# Expanders.net
KiCad netlist of a schematic drawn in Altium Designer
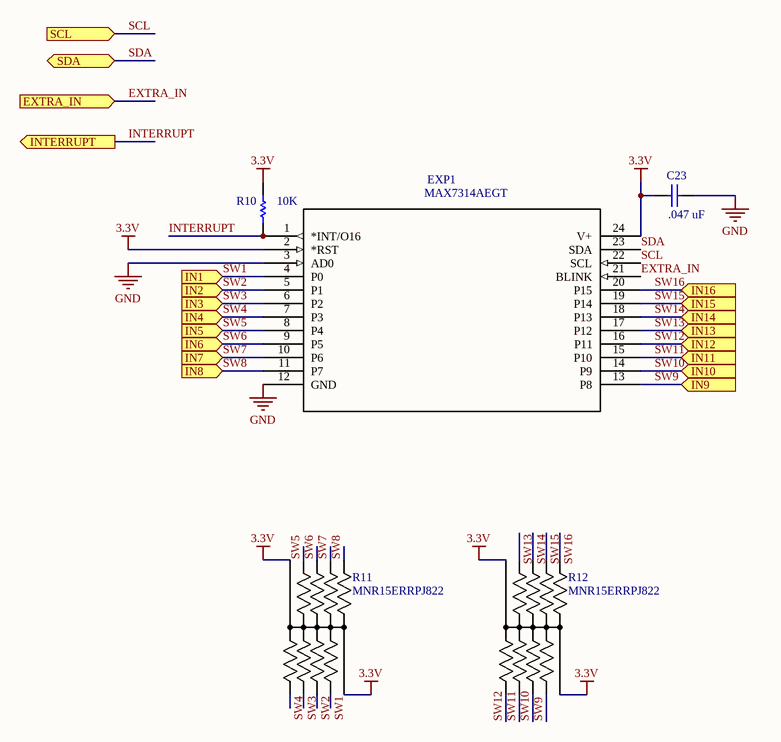
[diagram p0: Expanders.SchDoc]

(export (version "E")
  (design (tool "Eeschema 10.0.6"))
  (components
    (comp (ref "C23")
      (value ".047 uF")
      (footprint "C0805")
      (description "Capacitor")
      (fields (field (name "Comment") "Cap") (field (name "PUBLISHER") "Altium Limited"))
      (libsource (lib "Miscellaneous Devices") (part "Cap"))
    )
    (comp (ref "EXP1")
      (value "MAX7314AEGT")
      (footprint "21-0055H_24")
      (description "Interface IC - I/O extensions Maxim Integrated MAX7314AEG%2B PWM I%C2%B2C 400 kHz QSOP 24")
      (fields (field (name "MP") "MAX7314AEG+") (field (name "MF") "Maxim Integrated"))
      (libsource (lib "MAX7314AEGT") (part "MAX7314AEGT"))
    )
    (comp (ref "R10")
      (value "10K")
      (footprint "6-0805_N")
      (description "Resistor")
      (fields (field (name "Comment") "R5") (field (name "PUBLISHER") "Altium Limited"))
      (libsource (lib "Miscellaneous Devices") (part "Res1"))
    )
    (comp (ref "R11")
      (value "MNR15ERRPJ822")
      (footprint "MNR15")
      (description "Imported")
      (libsource (lib "surfacemountresarray") (part "MNR15ERRPJ822"))
    )
    (comp (ref "R12")
      (value "MNR15ERRPJ822")
      (footprint "MNR15")
      (description "Imported")
      (libsource (lib "surfacemountresarray") (part "MNR15ERRPJ822"))
    )
  )
  (nets
    (net (code "1") (name "/EXTRA_IN") (class "Default")
      (node (ref "EXP1") (pin "21") (pinfunction "BLINK_21") (pintype "input"))
    )
    (net (code "2") (name "/INTERRUPT") (class "Default")
      (node (ref "EXP1") (pin "1") (pinfunction "*INT/O16_1") (pintype "output"))
      (node (ref "R10") (pin "1") (pinfunction "1_1") (pintype "passive"))
    )
    (net (code "3") (name "/SCL") (class "Default")
      (node (ref "EXP1") (pin "22") (pinfunction "SCL_22") (pintype "input"))
    )
    (net (code "4") (name "/SDA") (class "Default")
      (node (ref "EXP1") (pin "23") (pinfunction "SDA_23") (pintype "passive"))
    )
    (net (code "5") (name "/SW1") (class "Default")
      (node (ref "EXP1") (pin "4") (pinfunction "P0_4") (pintype "passive"))
      (node (ref "R11") (pin "4") (pinfunction "4_4") (pintype "passive"))
    )
    (net (code "6") (name "/SW2") (class "Default")
      (node (ref "EXP1") (pin "5") (pinfunction "P1_5") (pintype "passive"))
      (node (ref "R11") (pin "3") (pinfunction "3_3") (pintype "passive"))
    )
    (net (code "7") (name "/SW3") (class "Default")
      (node (ref "EXP1") (pin "6") (pinfunction "P2_6") (pintype "passive"))
      (node (ref "R11") (pin "2") (pinfunction "2_2") (pintype "passive"))
    )
    (net (code "8") (name "/SW4") (class "Default")
      (node (ref "EXP1") (pin "7") (pinfunction "P3_7") (pintype "passive"))
      (node (ref "R11") (pin "1") (pinfunction "1_1") (pintype "passive"))
    )
    (net (code "9") (name "/SW5") (class "Default")
      (node (ref "EXP1") (pin "8") (pinfunction "P4_8") (pintype "passive"))
      (node (ref "R11") (pin "9") (pinfunction "9_9") (pintype "passive"))
    )
    (net (code "10") (name "/SW6") (class "Default")
      (node (ref "EXP1") (pin "9") (pinfunction "P5_9") (pintype "passive"))
      (node (ref "R11") (pin "8") (pinfunction "8_8") (pintype "passive"))
    )
    (net (code "11") (name "/SW7") (class "Default")
      (node (ref "EXP1") (pin "10") (pinfunction "P6_10") (pintype "passive"))
      (node (ref "R11") (pin "7") (pinfunction "7_7") (pintype "passive"))
    )
    (net (code "12") (name "/SW8") (class "Default")
      (node (ref "EXP1") (pin "11") (pinfunction "P7_11") (pintype "passive"))
      (node (ref "R11") (pin "6") (pinfunction "6_6") (pintype "passive"))
    )
    (net (code "13") (name "/SW9") (class "Default")
      (node (ref "EXP1") (pin "13") (pinfunction "P8_13") (pintype "passive"))
      (node (ref "R12") (pin "4") (pinfunction "4_4") (pintype "passive"))
    )
    (net (code "14") (name "/SW10") (class "Default")
      (node (ref "EXP1") (pin "14") (pinfunction "P9_14") (pintype "passive"))
      (node (ref "R12") (pin "3") (pinfunction "3_3") (pintype "passive"))
    )
    (net (code "15") (name "/SW11") (class "Default")
      (node (ref "EXP1") (pin "15") (pinfunction "P10_15") (pintype "passive"))
      (node (ref "R12") (pin "2") (pinfunction "2_2") (pintype "passive"))
    )
    (net (code "16") (name "/SW12") (class "Default")
      (node (ref "EXP1") (pin "16") (pinfunction "P11_16") (pintype "passive"))
      (node (ref "R12") (pin "1") (pinfunction "1_1") (pintype "passive"))
    )
    (net (code "17") (name "/SW13") (class "Default")
      (node (ref "EXP1") (pin "17") (pinfunction "P12_17") (pintype "passive"))
      (node (ref "R12") (pin "9") (pinfunction "9_9") (pintype "passive"))
    )
    (net (code "18") (name "/SW14") (class "Default")
      (node (ref "EXP1") (pin "18") (pinfunction "P13_18") (pintype "passive"))
      (node (ref "R12") (pin "8") (pinfunction "8_8") (pintype "passive"))
    )
    (net (code "19") (name "/SW15") (class "Default")
      (node (ref "EXP1") (pin "19") (pinfunction "P14_19") (pintype "passive"))
      (node (ref "R12") (pin "7") (pinfunction "7_7") (pintype "passive"))
    )
    (net (code "20") (name "/SW16") (class "Default")
      (node (ref "EXP1") (pin "20") (pinfunction "P15_20") (pintype "passive"))
      (node (ref "R12") (pin "6") (pinfunction "6_6") (pintype "passive"))
    )
    (net (code "21") (name "3.3V") (class "Default")
      (node (ref "C23") (pin "1") (pinfunction "1_1") (pintype "passive"))
      (node (ref "EXP1") (pin "2") (pinfunction "*RST_2") (pintype "input"))
      (node (ref "EXP1") (pin "24") (pinfunction "V+_24") (pintype "power_in"))
      (node (ref "R10") (pin "2") (pinfunction "2_2") (pintype "passive"))
      (node (ref "R11") (pin "10") (pinfunction "10_10") (pintype "passive"))
      (node (ref "R11") (pin "5") (pinfunction "5_5") (pintype "passive"))
      (node (ref "R12") (pin "10") (pinfunction "10_10") (pintype "passive"))
      (node (ref "R12") (pin "5") (pinfunction "5_5") (pintype "passive"))
    )
    (net (code "22") (name "GND") (class "Default")
      (node (ref "C23") (pin "2") (pinfunction "2_2") (pintype "passive"))
      (node (ref "EXP1") (pin "12") (pinfunction "GND_12") (pintype "power_in"))
      (node (ref "EXP1") (pin "3") (pinfunction "AD0_3") (pintype "input"))
    )
  )
)
